# EIS_Main_Power.net
KiCad netlist of a schematic drawn in Altium Designer
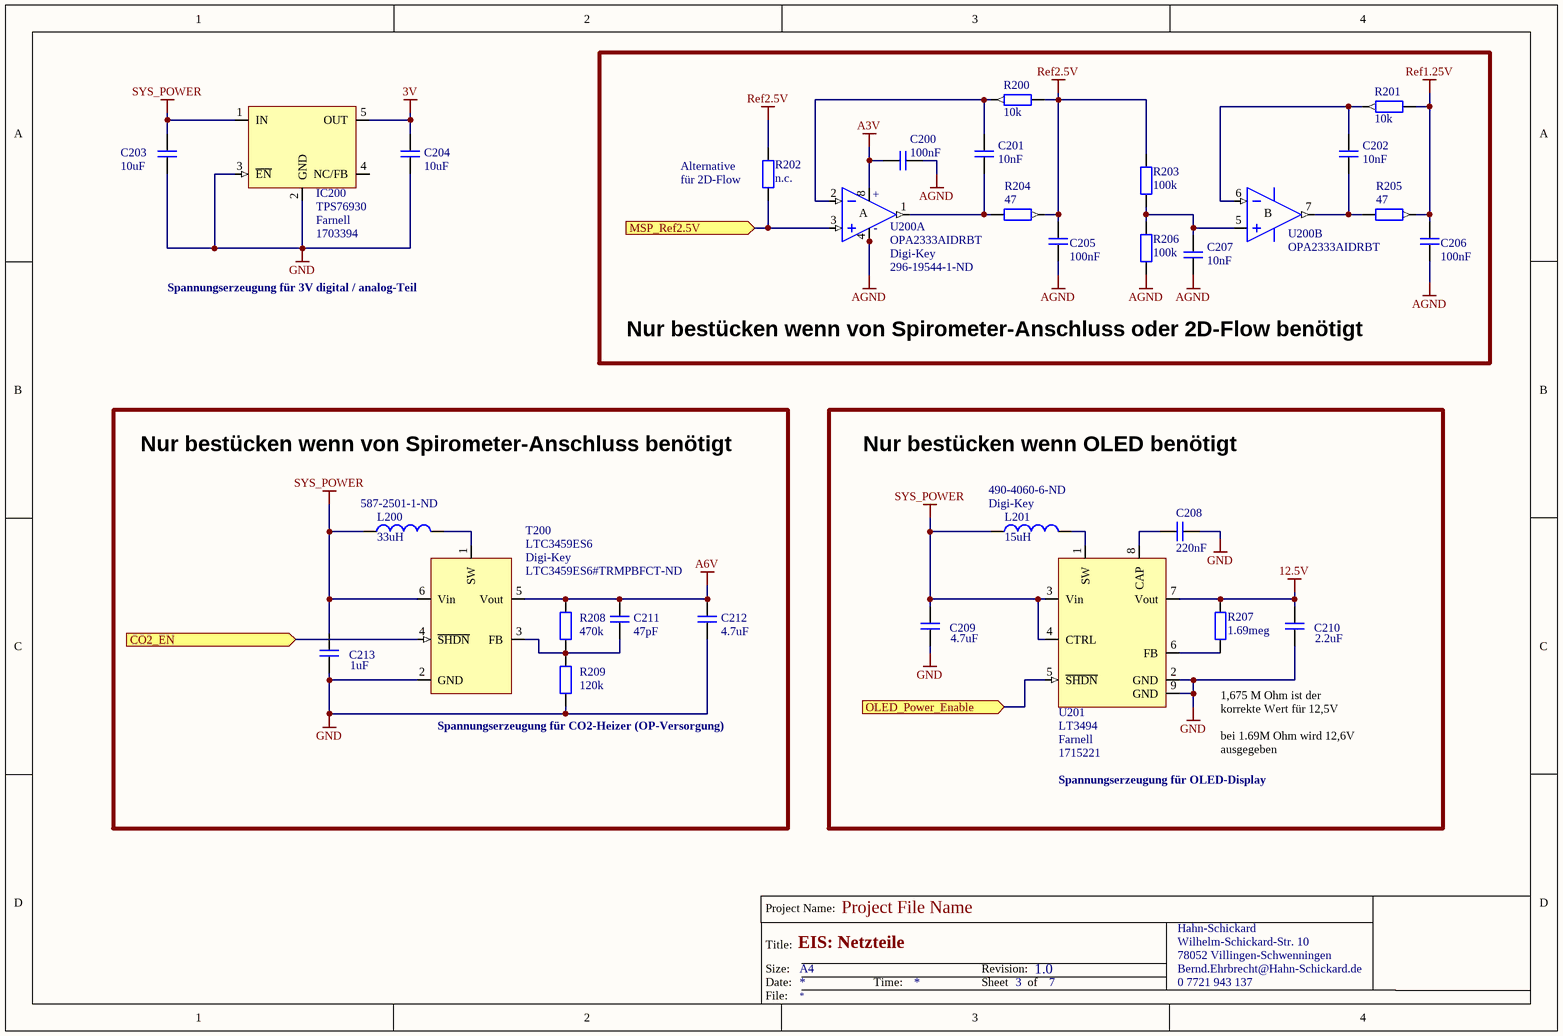
[diagram p0: EIS_Main_Power.SchDoc]

(export (version "E")
  (design (tool "Eeschema 10.0.6"))
  (components
    (comp (ref "C200")
      (value "100nF")
      (footprint "CAPC1608N")
      (libsource (lib "My_Schlib_6_15") (part "Kondensator SMD Keramik"))
    )
    (comp (ref "C201")
      (value "10nF")
      (footprint "CAPC1608N")
      (libsource (lib "My_Schlib_6_15") (part "Kondensator SMD Keramik"))
    )
    (comp (ref "C202")
      (value "10nF")
      (footprint "CAPC1608N")
      (libsource (lib "My_Schlib_6_15") (part "Kondensator SMD Keramik"))
    )
    (comp (ref "C203")
      (value "10uF")
      (footprint "CAPC1608N")
      (libsource (lib "My_Schlib_6_15") (part "Kondensator SMD Keramik"))
    )
    (comp (ref "C204")
      (value "10uF")
      (footprint "CAPC1608N")
      (libsource (lib "My_Schlib_6_15") (part "Kondensator SMD Keramik"))
    )
    (comp (ref "C205")
      (value "100nF")
      (footprint "CAPC1608N")
      (libsource (lib "My_Schlib_6_15") (part "Kondensator SMD Keramik"))
    )
    (comp (ref "C206")
      (value "100nF")
      (footprint "CAPC1608N")
      (libsource (lib "My_Schlib_6_15") (part "Kondensator SMD Keramik"))
    )
    (comp (ref "C207")
      (value "10nF")
      (footprint "CAPC1608N")
      (libsource (lib "My_Schlib_6_15") (part "Kondensator SMD Keramik"))
    )
    (comp (ref "C208")
      (value "220nF")
      (footprint "CAPC1608N")
      (libsource (lib "My_Schlib_6_18") (part "Kondensator SMD Keramik"))
    )
    (comp (ref "C209")
      (value "4.7uF")
      (footprint "CAPC1608N")
      (libsource (lib "My_Schlib_6_18") (part "Kondensator SMD Keramik"))
    )
    (comp (ref "C210")
      (value "2.2uF")
      (footprint "CAPC1608N")
      (libsource (lib "My_Schlib_6_18") (part "Kondensator SMD Keramik"))
    )
    (comp (ref "C211")
      (value "47pF")
      (footprint "CAPC1608N")
      (libsource (lib "My_Schlib_6_18") (part "Kondensator SMD Keramik"))
    )
    (comp (ref "C212")
      (value "4.7uF")
      (footprint "CAPC1608N")
      (libsource (lib "My_Schlib_6_18") (part "Kondensator SMD Keramik"))
    )
    (comp (ref "C213")
      (value "1uF")
      (footprint "CAPC1608N")
      (libsource (lib "My_Schlib_6_18") (part "Kondensator SMD Keramik"))
    )
    (comp (ref "IC200")
      (value "TPS76930")
      (footprint "TI-DBV5 (SOT23-5)")
      (description "Low Output, Adjustable, Ultralow-Power, 100-mA Low Dropout Linear Regulator")
      (fields
        (field (name "SUPPLIER 1") "Farnell")
        (field (name "SUPPLIER PART NUMBER 1") "1703394")
        (field (name "PUBLISHER") "HSG Selvakumar Palanichamy")
      )
      (libsource (lib "MetaSensClampOn_BT") (part "TPS76930"))
    )
    (comp (ref "L200")
      (value "33uH")
      (footprint "RESC2012N")
      (description "Inductor")
      (fields
        (field (name "SUPPLIER PART NUMBER 1") "587-2501-1-ND")
        (field (name "PUBLISHER") "Altium Limited")
      )
      (libsource (lib "Miscellaneous Devices") (part "Inductor"))
    )
    (comp (ref "L201")
      (value "15uH")
      (footprint "INDC3225N")
      (description "Inductor")
      (fields
        (field (name "SUPPLIER 1") "Digi-Key")
        (field (name "SUPPLIER PART NUMBER 1") "490-4060-6-ND")
        (field (name "PUBLISHER") "Altium Limited")
      )
      (libsource (lib "Miscellaneous Devices") (part "Inductor"))
    )
    (comp (ref "R200")
      (value "10k")
      (footprint "RESC1608N")
      (libsource (lib "My_Schlib_6_15") (part "Widerstand SMD"))
    )
    (comp (ref "R201")
      (value "10k")
      (footprint "RESC1608N")
      (libsource (lib "My_Schlib_6_15") (part "Widerstand SMD"))
    )
    (comp (ref "R202")
      (value "n.c.")
      (footprint "RESC1608N")
      (libsource (lib "My_Schlib_6_15") (part "Widerstand SMD"))
    )
    (comp (ref "R203")
      (value "100k")
      (footprint "RESC1608N")
      (libsource (lib "My_Schlib_6_15") (part "Widerstand SMD"))
    )
    (comp (ref "R204")
      (value "47")
      (footprint "RESC1608N")
      (libsource (lib "My_Schlib_6_15") (part "Widerstand SMD"))
    )
    (comp (ref "R205")
      (value "47")
      (footprint "RESC1608N")
      (libsource (lib "My_Schlib_6_15") (part "Widerstand SMD"))
    )
    (comp (ref "R206")
      (value "100k")
      (footprint "RESC1608N")
      (libsource (lib "My_Schlib_6_15") (part "Widerstand SMD"))
    )
    (comp (ref "R207")
      (value "1.69meg")
      (footprint "RESC1608N")
      (libsource (lib "My_Schlib_6_15") (part "Widerstand SMD"))
    )
    (comp (ref "R208")
      (value "470k")
      (footprint "RESC1608N")
      (libsource (lib "My_Schlib_6_15") (part "Widerstand SMD"))
    )
    (comp (ref "R209")
      (value "120k")
      (footprint "RESC1608N")
      (libsource (lib "My_Schlib_6_15") (part "Widerstand SMD"))
    )
    (comp (ref "T200")
      (value "LTC3459ES6")
      (footprint "TSOT23 - 6")
      (fields
        (field (name "SUPPLIER 1") "Digi-Key")
        (field (name "SUPPLIER PART NUMBER 1") "LTC3459ES6#TRMPBFCT-ND")
      )
      (libsource (lib "Spannung Wandler - LTC3459ES6") (part "Spannung Wandler - LTC3459ES6"))
    )
    (comp (ref "U200")
      (value "OPA2333AIDRBT")
      (footprint "TI DRB (S-PVON-N8)")
      (description "Dual micro Power OP")
      (fields
        (field (name "SUPPLIER 1") "Digi-Key")
        (field (name "SUPPLIER PART NUMBER 1") "296-19544-1-ND")
        (field (name "09_ERSTELLER") "HSG Jürgen Merz")
      )
      (libsource (lib "MetaSensClampOn_BT") (part "OPA2333AIDRBT"))
    )
    (comp (ref "U201")
      (value "LT3494")
      (footprint "DFN-DDB-8")
      (description "Bost-Konverter")
      (fields (field (name "SUPPLIER 1") "Farnell") (field (name "SUPPLIER PART NUMBER 1") "1715221"))
      (libsource (lib "MetaSensClampOn_BT") (part "LT3494"))
    )
  )
  (nets
    (net (code "1") (name "/CO2_EN") (class "Default")
      (node (ref "T200") (pin "4") (pinfunction "~{SHDN}_4") (pintype "input"))
    )
    (net (code "2") (name "/MSP_Ref2.5V") (class "Default")
      (node (ref "R202") (pin "1") (pinfunction "1_1") (pintype "passive"))
      (node (ref "U200") (pin "3") (pinfunction "IN1+_3") (pintype "input"))
    )
    (net (code "3") (name "/OLED_Power_Enable") (class "Default")
      (node (ref "U201") (pin "5") (pinfunction "~{SHDN}_5") (pintype "input"))
    )
    (net (code "4") (name "3V") (class "Default")
      (node (ref "C204") (pin "2") (pinfunction "2_2") (pintype "passive"))
      (node (ref "IC200") (pin "5") (pinfunction "OUT_5") (pintype "power_in"))
    )
    (net (code "5") (name "12.5V") (class "Default")
      (node (ref "C210") (pin "2") (pinfunction "2_2") (pintype "passive"))
      (node (ref "R207") (pin "2") (pinfunction "2_2") (pintype "output"))
      (node (ref "U201") (pin "7") (pinfunction "Vout_7") (pintype "power_in"))
    )
    (net (code "6") (name "A3V") (class "Default")
      (node (ref "C200") (pin "1") (pinfunction "1_1") (pintype "passive"))
      (node (ref "U200") (pin "8") (pinfunction "V+_8") (pintype "power_in"))
    )
    (net (code "7") (name "A6V") (class "Default")
      (node (ref "C211") (pin "2") (pinfunction "2_2") (pintype "passive"))
      (node (ref "C212") (pin "2") (pinfunction "2_2") (pintype "passive"))
      (node (ref "R208") (pin "2") (pinfunction "2_2") (pintype "output"))
      (node (ref "T200") (pin "5") (pinfunction "Vout_5") (pintype "power_in"))
    )
    (net (code "8") (name "AGND") (class "Default")
      (node (ref "C200") (pin "2") (pinfunction "2_2") (pintype "passive"))
      (node (ref "C205") (pin "1") (pinfunction "1_1") (pintype "passive"))
      (node (ref "C206") (pin "1") (pinfunction "1_1") (pintype "passive"))
      (node (ref "C207") (pin "1") (pinfunction "1_1") (pintype "passive"))
      (node (ref "R206") (pin "1") (pinfunction "1_1") (pintype "passive"))
      (node (ref "U200") (pin "4") (pinfunction "V-_4") (pintype "power_in"))
      (node (ref "U200") (pin "9") (pinfunction "tp1_9") (pintype "passive"))
    )
    (net (code "9") (name "GND") (class "Default")
      (node (ref "C203") (pin "1") (pinfunction "1_1") (pintype "passive"))
      (node (ref "C204") (pin "1") (pinfunction "1_1") (pintype "passive"))
      (node (ref "C208") (pin "1") (pinfunction "1_1") (pintype "passive"))
      (node (ref "C209") (pin "1") (pinfunction "1_1") (pintype "passive"))
      (node (ref "C210") (pin "1") (pinfunction "1_1") (pintype "passive"))
      (node (ref "C212") (pin "1") (pinfunction "1_1") (pintype "passive"))
      (node (ref "C213") (pin "1") (pinfunction "1_1") (pintype "passive"))
      (node (ref "IC200") (pin "2") (pinfunction "GND_2") (pintype "passive"))
      (node (ref "IC200") (pin "3") (pinfunction "~{EN}_3") (pintype "input"))
      (node (ref "R209") (pin "1") (pinfunction "1_1") (pintype "passive"))
      (node (ref "T200") (pin "2") (pinfunction "GND_2") (pintype "power_in"))
      (node (ref "U201") (pin "2") (pinfunction "GND_2") (pintype "passive"))
      (node (ref "U201") (pin "9") (pinfunction "GND_9") (pintype "passive"))
    )
    (net (code "10") (name "Net-(T200-FB)") (class "Default")
      (node (ref "C211") (pin "1") (pinfunction "1_1") (pintype "passive"))
      (node (ref "R208") (pin "1") (pinfunction "1_1") (pintype "passive"))
      (node (ref "R209") (pin "2") (pinfunction "2_2") (pintype "output"))
      (node (ref "T200") (pin "3") (pinfunction "FB_3") (pintype "passive"))
    )
    (net (code "11") (name "Net-(T200-SW)") (class "Default")
      (node (ref "L200") (pin "2") (pinfunction "2_2") (pintype "passive"))
      (node (ref "T200") (pin "1") (pinfunction "SW_1") (pintype "passive"))
    )
    (net (code "12") (name "Net-(U200A-IN1-)") (class "Default")
      (node (ref "C201") (pin "2") (pinfunction "2_2") (pintype "passive"))
      (node (ref "R200") (pin "2") (pinfunction "2_2") (pintype "output"))
      (node (ref "U200") (pin "2") (pinfunction "IN1-_2") (pintype "input"))
    )
    (net (code "13") (name "Net-(U200A-OUT1)") (class "Default")
      (node (ref "C201") (pin "1") (pinfunction "1_1") (pintype "passive"))
      (node (ref "R204") (pin "1") (pinfunction "1_1") (pintype "passive"))
      (node (ref "U200") (pin "1") (pinfunction "OUT1_1") (pintype "output"))
    )
    (net (code "14") (name "Net-(U200B-IN1+)") (class "Default")
      (node (ref "C207") (pin "2") (pinfunction "2_2") (pintype "passive"))
      (node (ref "R203") (pin "1") (pinfunction "1_1") (pintype "passive"))
      (node (ref "R206") (pin "2") (pinfunction "2_2") (pintype "output"))
      (node (ref "U200") (pin "5") (pinfunction "IN1+_5") (pintype "input"))
    )
    (net (code "15") (name "Net-(U200B-IN1-)") (class "Default")
      (node (ref "C202") (pin "2") (pinfunction "2_2") (pintype "passive"))
      (node (ref "R201") (pin "2") (pinfunction "2_2") (pintype "output"))
      (node (ref "U200") (pin "6") (pinfunction "IN1-_6") (pintype "input"))
    )
    (net (code "16") (name "Net-(U200B-OUT1)") (class "Default")
      (node (ref "C202") (pin "1") (pinfunction "1_1") (pintype "passive"))
      (node (ref "R205") (pin "1") (pinfunction "1_1") (pintype "passive"))
      (node (ref "U200") (pin "7") (pinfunction "OUT1_7") (pintype "output"))
    )
    (net (code "17") (name "Net-(U201-CAP)") (class "Default")
      (node (ref "C208") (pin "2") (pinfunction "2_2") (pintype "passive"))
      (node (ref "U201") (pin "8") (pinfunction "CAP_8") (pintype "passive"))
    )
    (net (code "18") (name "Net-(U201-FB)") (class "Default")
      (node (ref "R207") (pin "1") (pinfunction "1_1") (pintype "passive"))
      (node (ref "U201") (pin "6") (pinfunction "FB_6") (pintype "passive"))
    )
    (net (code "19") (name "Net-(U201-SW)") (class "Default")
      (node (ref "L201") (pin "2") (pinfunction "2_2") (pintype "passive"))
      (node (ref "U201") (pin "1") (pinfunction "SW_1") (pintype "passive"))
    )
    (net (code "20") (name "Ref1.25V") (class "Default")
      (node (ref "C206") (pin "2") (pinfunction "2_2") (pintype "passive"))
      (node (ref "R201") (pin "1") (pinfunction "1_1") (pintype "passive"))
      (node (ref "R205") (pin "2") (pinfunction "2_2") (pintype "output"))
    )
    (net (code "21") (name "Ref2.5V") (class "Default")
      (node (ref "C205") (pin "2") (pinfunction "2_2") (pintype "passive"))
      (node (ref "R200") (pin "1") (pinfunction "1_1") (pintype "passive"))
      (node (ref "R202") (pin "2") (pinfunction "2_2") (pintype "output"))
      (node (ref "R203") (pin "2") (pinfunction "2_2") (pintype "output"))
      (node (ref "R204") (pin "2") (pinfunction "2_2") (pintype "output"))
    )
    (net (code "22") (name "SYS_POWER") (class "Default")
      (node (ref "C203") (pin "2") (pinfunction "2_2") (pintype "passive"))
      (node (ref "C209") (pin "2") (pinfunction "2_2") (pintype "passive"))
      (node (ref "C213") (pin "2") (pinfunction "2_2") (pintype "passive"))
      (node (ref "IC200") (pin "1") (pinfunction "IN_1") (pintype "power_in"))
      (node (ref "L200") (pin "1") (pinfunction "1_1") (pintype "passive"))
      (node (ref "L201") (pin "1") (pinfunction "1_1") (pintype "passive"))
      (node (ref "T200") (pin "6") (pinfunction "Vin_6") (pintype "power_in"))
      (node (ref "U201") (pin "3") (pinfunction "Vin_3") (pintype "power_in"))
      (node (ref "U201") (pin "4") (pinfunction "CTRL_4") (pintype "passive"))
    )
    (net (code "23") (name "unconnected-(IC200-NC{slash}FB-Pad4)") (class "Default")
      (node (ref "IC200") (pin "4") (pinfunction "NC/FB_4") (pintype "passive"))
    )
  )
)
